# dac.net
KiCad netlist of a schematic drawn in Altium Designer
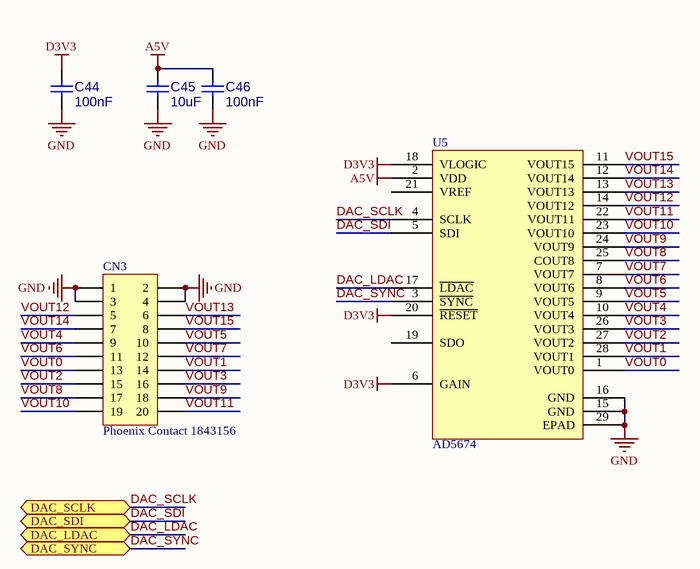
[diagram p0: dac.SchDoc]

(export (version "E")
  (design (tool "Eeschema 10.0.6"))
  (components
    (comp (ref "C44")
      (value "100nF")
      (footprint "C0603")
      (description "GRM155R71C104KA88J")
      (fields (field (name "PUBLISHER") "Altium Limited"))
      (libsource (lib "Miscellaneous Devices") (part "Cap"))
    )
    (comp (ref "C45")
      (value "10uF")
      (footprint "C1206N")
      (description "Capacitor")
      (fields (field (name "PUBLISHER") "Altium Limited"))
      (libsource (lib "Miscellaneous Devices") (part "Cap"))
    )
    (comp (ref "C46")
      (value "100nF")
      (footprint "C0603")
      (description "GRM155R71C104KA88J")
      (fields (field (name "PUBLISHER") "Altium Limited"))
      (libsource (lib "Miscellaneous Devices") (part "Cap"))
    )
    (comp (ref "CN3")
      (value "Phoenix Contact 1843156")
      (footprint "PHOENIX1843156")
      (description "Header, 10-Pin, Dual row")
      (fields (field (name "PUBLISHER") "Altium Limited"))
      (libsource (lib "Miscellaneous Connectors") (part "Header 10X2"))
    )
    (comp (ref "U5")
      (value "AD5674")
      (footprint "PNI-MAGI2C")
      (libsource (lib "PowerComps-more") (part "AD5674"))
    )
  )
  (nets
    (net (code "1") (name "/DAC_LDAC") (class "Default")
      (node (ref "U5") (pin "17") (pinfunction "~{LDAC}_17") (pintype "passive"))
    )
    (net (code "2") (name "/DAC_SCLK") (class "Default")
      (node (ref "U5") (pin "4") (pinfunction "SCLK_4") (pintype "passive"))
    )
    (net (code "3") (name "/DAC_SDI") (class "Default")
      (node (ref "U5") (pin "5") (pinfunction "SDI_5") (pintype "passive"))
    )
    (net (code "4") (name "/DAC_SYNC") (class "Default")
      (node (ref "U5") (pin "3") (pinfunction "~{SYNC}_3") (pintype "passive"))
    )
    (net (code "5") (name "/VOUT0") (class "Default")
      (node (ref "CN3") (pin "13") (pinfunction "13_13") (pintype "passive"))
      (node (ref "U5") (pin "1") (pinfunction "VOUT0_1") (pintype "passive"))
    )
    (net (code "6") (name "/VOUT1") (class "Default")
      (node (ref "CN3") (pin "14") (pinfunction "14_14") (pintype "passive"))
      (node (ref "U5") (pin "28") (pinfunction "VOUT1_28") (pintype "passive"))
    )
    (net (code "7") (name "/VOUT2") (class "Default")
      (node (ref "CN3") (pin "15") (pinfunction "15_15") (pintype "passive"))
      (node (ref "U5") (pin "27") (pinfunction "VOUT2_27") (pintype "passive"))
    )
    (net (code "8") (name "/VOUT3") (class "Default")
      (node (ref "CN3") (pin "16") (pinfunction "16_16") (pintype "passive"))
      (node (ref "U5") (pin "26") (pinfunction "VOUT3_26") (pintype "passive"))
    )
    (net (code "9") (name "/VOUT4") (class "Default")
      (node (ref "CN3") (pin "9") (pinfunction "9_9") (pintype "passive"))
      (node (ref "U5") (pin "10") (pinfunction "VOUT4_10") (pintype "passive"))
    )
    (net (code "10") (name "/VOUT5") (class "Default")
      (node (ref "CN3") (pin "10") (pinfunction "10_10") (pintype "passive"))
      (node (ref "U5") (pin "9") (pinfunction "VOUT5_9") (pintype "passive"))
    )
    (net (code "11") (name "/VOUT6") (class "Default")
      (node (ref "CN3") (pin "11") (pinfunction "11_11") (pintype "passive"))
      (node (ref "U5") (pin "8") (pinfunction "VOUT6_8") (pintype "passive"))
    )
    (net (code "12") (name "/VOUT7") (class "Default")
      (node (ref "CN3") (pin "12") (pinfunction "12_12") (pintype "passive"))
      (node (ref "U5") (pin "7") (pinfunction "VOUT7_7") (pintype "passive"))
    )
    (net (code "13") (name "/VOUT8") (class "Default")
      (node (ref "CN3") (pin "17") (pinfunction "17_17") (pintype "passive"))
      (node (ref "U5") (pin "25") (pinfunction "COUT8_25") (pintype "passive"))
    )
    (net (code "14") (name "/VOUT9") (class "Default")
      (node (ref "CN3") (pin "18") (pinfunction "18_18") (pintype "passive"))
      (node (ref "U5") (pin "24") (pinfunction "VOUT9_24") (pintype "passive"))
    )
    (net (code "15") (name "/VOUT10") (class "Default")
      (node (ref "CN3") (pin "19") (pinfunction "19_19") (pintype "passive"))
      (node (ref "U5") (pin "23") (pinfunction "VOUT10_23") (pintype "passive"))
    )
    (net (code "16") (name "/VOUT11") (class "Default")
      (node (ref "CN3") (pin "20") (pinfunction "20_20") (pintype "passive"))
      (node (ref "U5") (pin "22") (pinfunction "VOUT11_22") (pintype "passive"))
    )
    (net (code "17") (name "/VOUT12") (class "Default")
      (node (ref "CN3") (pin "5") (pinfunction "5_5") (pintype "passive"))
      (node (ref "U5") (pin "14") (pinfunction "VOUT12_14") (pintype "passive"))
    )
    (net (code "18") (name "/VOUT13") (class "Default")
      (node (ref "CN3") (pin "6") (pinfunction "6_6") (pintype "passive"))
      (node (ref "U5") (pin "13") (pinfunction "VOUT13_13") (pintype "passive"))
    )
    (net (code "19") (name "/VOUT14") (class "Default")
      (node (ref "CN3") (pin "7") (pinfunction "7_7") (pintype "passive"))
      (node (ref "U5") (pin "12") (pinfunction "VOUT14_12") (pintype "passive"))
    )
    (net (code "20") (name "/VOUT15") (class "Default")
      (node (ref "CN3") (pin "8") (pinfunction "8_8") (pintype "passive"))
      (node (ref "U5") (pin "11") (pinfunction "VOUT15_11") (pintype "passive"))
    )
    (net (code "21") (name "A5V") (class "Default")
      (node (ref "C45") (pin "1") (pinfunction "1_1") (pintype "passive"))
      (node (ref "C46") (pin "1") (pinfunction "1_1") (pintype "passive"))
      (node (ref "U5") (pin "2") (pinfunction "VDD_2") (pintype "passive"))
    )
    (net (code "22") (name "D3V3") (class "Default")
      (node (ref "C44") (pin "1") (pinfunction "1_1") (pintype "passive"))
      (node (ref "U5") (pin "18") (pinfunction "VLOGIC_18") (pintype "passive"))
      (node (ref "U5") (pin "20") (pinfunction "~{RESET}_20") (pintype "passive"))
      (node (ref "U5") (pin "6") (pinfunction "GAIN_6") (pintype "passive"))
    )
    (net (code "23") (name "GND") (class "Default")
      (node (ref "C44") (pin "2") (pinfunction "2_2") (pintype "passive"))
      (node (ref "C45") (pin "2") (pinfunction "2_2") (pintype "passive"))
      (node (ref "C46") (pin "2") (pinfunction "2_2") (pintype "passive"))
      (node (ref "CN3") (pin "1") (pinfunction "1_1") (pintype "passive"))
      (node (ref "CN3") (pin "2") (pinfunction "2_2") (pintype "passive"))
      (node (ref "CN3") (pin "3") (pinfunction "3_3") (pintype "passive"))
      (node (ref "CN3") (pin "4") (pinfunction "4_4") (pintype "passive"))
      (node (ref "U5") (pin "15") (pinfunction "GND_15") (pintype "passive"))
      (node (ref "U5") (pin "16") (pinfunction "GND_16") (pintype "passive"))
      (node (ref "U5") (pin "29") (pinfunction "EPAD_29") (pintype "passive"))
    )
    (net (code "24") (name "unconnected-(U5-SDO-Pad19)") (class "Default")
      (node (ref "U5") (pin "19") (pinfunction "SDO_19") (pintype "passive"))
    )
    (net (code "25") (name "unconnected-(U5-VREF-Pad21)") (class "Default")
      (node (ref "U5") (pin "21") (pinfunction "VREF_21") (pintype "passive"))
    )
  )
)
